# ConectoresEntrada.net
KiCad netlist of a schematic drawn in Altium Designer
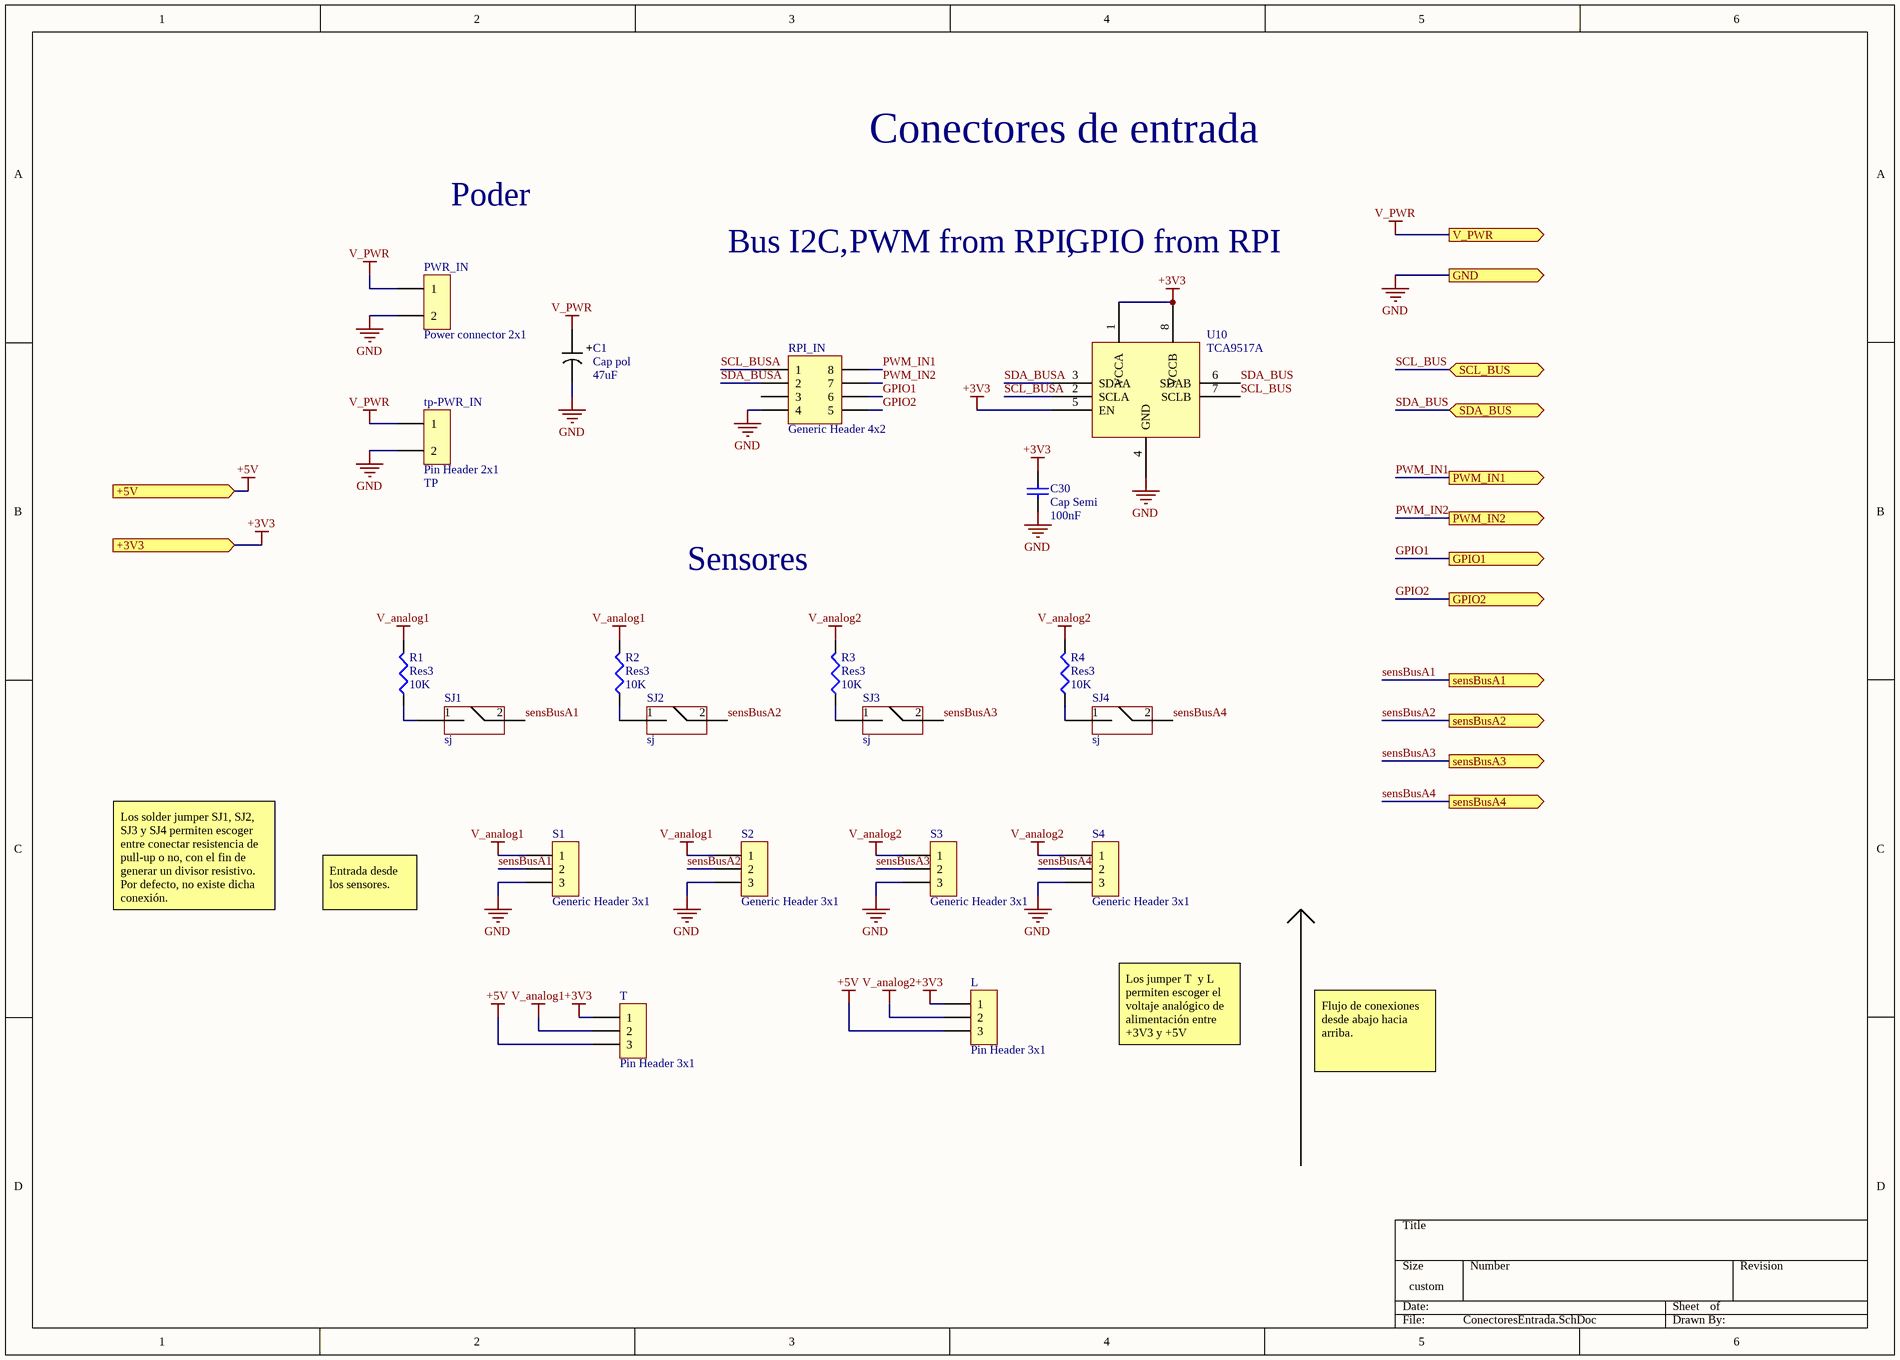
[diagram p0: ConectoresEntrada.SchDoc]

(export (version "E")
  (design (tool "Eeschema 10.0.6"))
  (components
    (comp (ref "C1")
      (value "Cap pol")
      (footprint "CAP_SMD_Electrolytic_10x10")
      (description "Electrolytic Aluminium Capacitor")
      (fields
        (field (name "MANUFACTURER") "Lelon")
        (field (name "MANUFACTURER PART NUMBER") "VEJ470M1HTR-1010")
        (field (name "ALTIUM_VALUE") "47uF")
      )
      (libsource (lib "IoWLabs") (part "Cap pol"))
    )
    (comp (ref "C30")
      (value "Cap Semi")
      (footprint "1608[0603]")
      (description "Capacitor (Semiconductor SIM Model)")
      (fields
        (field (name "ALTIUM_VALUE") "100nF")
        (field (name "MANUFACTURER") "Taiyo Yuden")
        (field (name "MANUFACTURER PART NUMBER") "UMK107B104KAHT")
        (field (name "PUBLISHER") "Altium Limited")
      )
      (libsource (lib "Miscellaneous Devices") (part "Cap Semi"))
    )
    (comp (ref "L")
      (value "Pin Header 3x1")
      (footprint "HDR-TH_3P-P2.54-V")
      (description "Pin Header 3pos, 1 row, 2.54 pitch")
      (fields
        (field (name "MANUFACTURER") "CJT(Changjiang Connectors)")
        (field (name "MANUFACTURER PART NUMBER") "A2541WV-3P")
      )
      (libsource (lib "IoWLabsConnectors") (part "Header - 3x1c"))
    )
    (comp (ref "PWR_IN")
      (value "Power connector 2x1")
      (footprint "CONN-TH_430450212")
      (description "Generic Header Power 2pos")
      (fields (field (name "MANUFACTURER") "MOLEX") (field (name "MANUFACTURER PART NUMBER") "430450212"))
      (libsource (lib "IoWLabsConnectors") (part "PC - 2X1"))
    )
    (comp (ref "R1")
      (value "Res3")
      (footprint "J1-0603")
      (description "Resistor")
      (fields
        (field (name "ALTIUM_VALUE") "10K")
        (field (name "MANUFACTURER") "PANASONIC")
        (field (name "MANUFACTURER PART NUMBER") "ERJPA3F1002V")
        (field (name "PUBLISHER") "Altium Limited")
      )
      (libsource (lib "Miscellaneous Devices") (part "Res3"))
    )
    (comp (ref "R2")
      (value "Res3")
      (footprint "J1-0603")
      (description "Resistor")
      (fields
        (field (name "ALTIUM_VALUE") "10K")
        (field (name "MANUFACTURER") "PANASONIC")
        (field (name "MANUFACTURER PART NUMBER") "ERJPA3F1002V")
        (field (name "PUBLISHER") "Altium Limited")
      )
      (libsource (lib "Miscellaneous Devices") (part "Res3"))
    )
    (comp (ref "R3")
      (value "Res3")
      (footprint "J1-0603")
      (description "Resistor")
      (fields
        (field (name "ALTIUM_VALUE") "10K")
        (field (name "MANUFACTURER") "PANASONIC")
        (field (name "MANUFACTURER PART NUMBER") "ERJPA3F1002V")
        (field (name "PUBLISHER") "Altium Limited")
      )
      (libsource (lib "Miscellaneous Devices") (part "Res3"))
    )
    (comp (ref "R4")
      (value "Res3")
      (footprint "J1-0603")
      (description "Resistor")
      (fields
        (field (name "ALTIUM_VALUE") "10K")
        (field (name "MANUFACTURER PART NUMBER") "ERJPA3F1002V")
        (field (name "MANUFACTURER") "PANASONIC")
        (field (name "PUBLISHER") "Altium Limited")
      )
      (libsource (lib "Miscellaneous Devices") (part "Res3"))
    )
    (comp (ref "RPI_IN")
      (value "Generic Header 4x2")
      (footprint "CONN-TH_8P-P2.54-V-M_15477608")
      (description "Generic Header 8 pos, 2 row, 2.54 pitch")
      (fields (field (name "MANUFACTURER") "MOLEX") (field (name "MANUFACTURER PART NUMBER") "15477608"))
      (libsource (lib "IoWLabsConnectors") (part "Header - 4x2"))
    )
    (comp (ref "S1")
      (value "Generic Header 3x1")
      (footprint "CONN-TH_A2547WV-3P")
      (description "Generic Header 3pos, 1 row, 2.54 pitch")
      (fields
        (field (name "MANUFACTURER") "CJT(Changjiang Connectors)")
        (field (name "MANUFACTURER PART NUMBER") "A2547WV-3P")
      )
      (libsource (lib "IoWLabsConnectors") (part "Header - 3x1"))
    )
    (comp (ref "S2")
      (value "Generic Header 3x1")
      (footprint "CONN-TH_A2547WV-3P")
      (description "Generic Header 3pos, 1 row, 2.54 pitch")
      (fields
        (field (name "MANUFACTURER") "CJT(Changjiang Connectors)")
        (field (name "MANUFACTURER PART NUMBER") "A2547WV-3P")
      )
      (libsource (lib "IoWLabsConnectors") (part "Header - 3x1"))
    )
    (comp (ref "S3")
      (value "Generic Header 3x1")
      (footprint "CONN-TH_A2547WV-3P")
      (description "Generic Header 3pos, 1 row, 2.54 pitch")
      (fields
        (field (name "MANUFACTURER") "CJT(Changjiang Connectors)")
        (field (name "MANUFACTURER PART NUMBER") "A2547WV-3P")
      )
      (libsource (lib "IoWLabsConnectors") (part "Header - 3x1"))
    )
    (comp (ref "S4")
      (value "Generic Header 3x1")
      (footprint "CONN-TH_A2547WV-3P")
      (description "Generic Header 3pos, 1 row, 2.54 pitch")
      (fields
        (field (name "MANUFACTURER") "CJT(Changjiang Connectors)")
        (field (name "MANUFACTURER PART NUMBER") "A2547WV-3P")
      )
      (libsource (lib "IoWLabsConnectors") (part "Header - 3x1"))
    )
    (comp (ref "SJ1")
      (value "sj")
      (footprint "SJ2")
      (description "solder jumper generic")
      (libsource (lib "IoWLabs") (part "Jumper"))
    )
    (comp (ref "SJ2")
      (value "sj")
      (footprint "SJ2")
      (description "solder jumper generic")
      (libsource (lib "IoWLabs") (part "Jumper"))
    )
    (comp (ref "SJ3")
      (value "sj")
      (footprint "SJ2")
      (description "solder jumper generic")
      (libsource (lib "IoWLabs") (part "Jumper"))
    )
    (comp (ref "SJ4")
      (value "sj")
      (footprint "SJ2")
      (description "solder jumper generic")
      (libsource (lib "IoWLabs") (part "Jumper"))
    )
    (comp (ref "T")
      (value "Pin Header 3x1")
      (footprint "HDR-TH_3P-P2.54-V")
      (description "Pin Header 3pos, 1 row, 2.54 pitch")
      (fields
        (field (name "MANUFACTURER") "CJT(Changjiang Connectors)")
        (field (name "MANUFACTURER PART NUMBER") "A2541WV-3P")
      )
      (libsource (lib "IoWLabsConnectors") (part "Header - 3x1c"))
    )
    (comp (ref "tp-PWR_IN")
      (value "Pin Header 2x1")
      (footprint "HDR-TH_P2.54-H-M_A2541WV-2P")
      (description "Pin Header 2pos, 1 row, 2.54 pitch")
      (fields
        (field (name "MANUFACTURER") "CJT(Changjiang Connectors)")
        (field (name "MANUFACTURER PART NUMBER") "A2541WV-2P")
      )
      (libsource (lib "IoWLabsConnectors") (part "Header - 2x1c"))
    )
    (comp (ref "U10")
      (value "TCA9517A")
      (footprint "VSSOP - 8")
      (description "VSSOP-8_3x3x065P Level Translators, Shifters RoHS")
      (fields
        (field (name "MANUFACTURER") "Texas Instruments")
        (field (name "MANUFACTURER PART NUMBER") "TCA9517ADGKR")
      )
      (libsource (lib "IoWLabs") (part "TCA9517A"))
    )
  )
  (nets
    (net (code "1") (name "+3V3") (class "Default")
      (node (ref "C30") (pin "2") (pinfunction "2_2") (pintype "passive"))
      (node (ref "L") (pin "1") (pinfunction "1_1") (pintype "passive"))
      (node (ref "T") (pin "1") (pinfunction "1_1") (pintype "passive"))
      (node (ref "U10") (pin "1") (pinfunction "VCCA_1") (pintype "passive"))
      (node (ref "U10") (pin "5") (pinfunction "EN_5") (pintype "passive"))
      (node (ref "U10") (pin "8") (pinfunction "VCCB_8") (pintype "passive"))
    )
    (net (code "2") (name "+5V") (class "Default")
      (node (ref "L") (pin "3") (pinfunction "3_3") (pintype "passive"))
      (node (ref "T") (pin "3") (pinfunction "3_3") (pintype "passive"))
    )
    (net (code "3") (name "/GPIO1") (class "Default")
      (node (ref "RPI_IN") (pin "6") (pinfunction "6_6") (pintype "passive"))
    )
    (net (code "4") (name "/GPIO2") (class "Default")
      (node (ref "RPI_IN") (pin "5") (pinfunction "5_5") (pintype "passive"))
    )
    (net (code "5") (name "/PWM_IN1") (class "Default")
      (node (ref "RPI_IN") (pin "8") (pinfunction "8_8") (pintype "passive"))
    )
    (net (code "6") (name "/PWM_IN2") (class "Default")
      (node (ref "RPI_IN") (pin "7") (pinfunction "7_7") (pintype "passive"))
    )
    (net (code "7") (name "/SCL_BUS") (class "Default")
      (node (ref "U10") (pin "7") (pinfunction "SCLB_7") (pintype "passive"))
    )
    (net (code "8") (name "/SCL_BUSA") (class "Default")
      (node (ref "RPI_IN") (pin "1") (pinfunction "1_1") (pintype "passive"))
      (node (ref "U10") (pin "2") (pinfunction "SCLA_2") (pintype "passive"))
    )
    (net (code "9") (name "/SDA_BUS") (class "Default")
      (node (ref "U10") (pin "6") (pinfunction "SDAB_6") (pintype "passive"))
    )
    (net (code "10") (name "/SDA_BUSA") (class "Default")
      (node (ref "RPI_IN") (pin "2") (pinfunction "2_2") (pintype "passive"))
      (node (ref "U10") (pin "3") (pinfunction "SDAA_3") (pintype "passive"))
    )
    (net (code "11") (name "/sensBusA1") (class "Default")
      (node (ref "S1") (pin "2") (pinfunction "2_2") (pintype "passive"))
      (node (ref "SJ1") (pin "2") (pinfunction "2_2") (pintype "passive"))
    )
    (net (code "12") (name "/sensBusA2") (class "Default")
      (node (ref "S2") (pin "2") (pinfunction "2_2") (pintype "passive"))
      (node (ref "SJ2") (pin "2") (pinfunction "2_2") (pintype "passive"))
    )
    (net (code "13") (name "/sensBusA3") (class "Default")
      (node (ref "S3") (pin "2") (pinfunction "2_2") (pintype "passive"))
      (node (ref "SJ3") (pin "2") (pinfunction "2_2") (pintype "passive"))
    )
    (net (code "14") (name "/sensBusA4") (class "Default")
      (node (ref "S4") (pin "2") (pinfunction "2_2") (pintype "passive"))
      (node (ref "SJ4") (pin "2") (pinfunction "2_2") (pintype "passive"))
    )
    (net (code "15") (name "GND") (class "Default")
      (node (ref "C1") (pin "1") (pinfunction "1_1") (pintype "passive"))
      (node (ref "C30") (pin "1") (pinfunction "1_1") (pintype "passive"))
      (node (ref "PWR_IN") (pin "2") (pinfunction "2_2") (pintype "passive"))
      (node (ref "RPI_IN") (pin "4") (pinfunction "4_4") (pintype "passive"))
      (node (ref "S1") (pin "3") (pinfunction "3_3") (pintype "passive"))
      (node (ref "S2") (pin "3") (pinfunction "3_3") (pintype "passive"))
      (node (ref "S3") (pin "3") (pinfunction "3_3") (pintype "passive"))
      (node (ref "S4") (pin "3") (pinfunction "3_3") (pintype "passive"))
      (node (ref "U10") (pin "4") (pinfunction "GND_4") (pintype "passive"))
      (node (ref "tp-PWR_IN") (pin "2") (pinfunction "2_2") (pintype "passive"))
    )
    (net (code "16") (name "Net-(R1-Pad1)") (class "Default")
      (node (ref "R1") (pin "1") (pinfunction "1_1") (pintype "passive"))
      (node (ref "SJ1") (pin "1") (pinfunction "1_1") (pintype "passive"))
    )
    (net (code "17") (name "Net-(R2-Pad1)") (class "Default")
      (node (ref "R2") (pin "1") (pinfunction "1_1") (pintype "passive"))
      (node (ref "SJ2") (pin "1") (pinfunction "1_1") (pintype "passive"))
    )
    (net (code "18") (name "Net-(R3-Pad1)") (class "Default")
      (node (ref "R3") (pin "1") (pinfunction "1_1") (pintype "passive"))
      (node (ref "SJ3") (pin "1") (pinfunction "1_1") (pintype "passive"))
    )
    (net (code "19") (name "Net-(R4-Pad1)") (class "Default")
      (node (ref "R4") (pin "1") (pinfunction "1_1") (pintype "passive"))
      (node (ref "SJ4") (pin "1") (pinfunction "1_1") (pintype "passive"))
    )
    (net (code "20") (name "V_PWR") (class "Default")
      (node (ref "C1") (pin "2") (pinfunction "2_2") (pintype "passive"))
      (node (ref "PWR_IN") (pin "1") (pinfunction "1_1") (pintype "passive"))
      (node (ref "tp-PWR_IN") (pin "1") (pinfunction "1_1") (pintype "passive"))
    )
    (net (code "21") (name "V_analog1") (class "Default")
      (node (ref "R1") (pin "2") (pinfunction "2_2") (pintype "passive"))
      (node (ref "R2") (pin "2") (pinfunction "2_2") (pintype "passive"))
      (node (ref "S1") (pin "1") (pinfunction "1_1") (pintype "passive"))
      (node (ref "S2") (pin "1") (pinfunction "1_1") (pintype "passive"))
      (node (ref "T") (pin "2") (pinfunction "2_2") (pintype "passive"))
    )
    (net (code "22") (name "V_analog2") (class "Default")
      (node (ref "L") (pin "2") (pinfunction "2_2") (pintype "passive"))
      (node (ref "R3") (pin "2") (pinfunction "2_2") (pintype "passive"))
      (node (ref "R4") (pin "2") (pinfunction "2_2") (pintype "passive"))
      (node (ref "S3") (pin "1") (pinfunction "1_1") (pintype "passive"))
      (node (ref "S4") (pin "1") (pinfunction "1_1") (pintype "passive"))
    )
    (net (code "23") (name "unconnected-(RPI_IN-Pad3)") (class "Default")
      (node (ref "RPI_IN") (pin "3") (pinfunction "3_3") (pintype "passive"))
    )
  )
)
